# TDR1.net
KiCad netlist of a schematic drawn in EAGLE
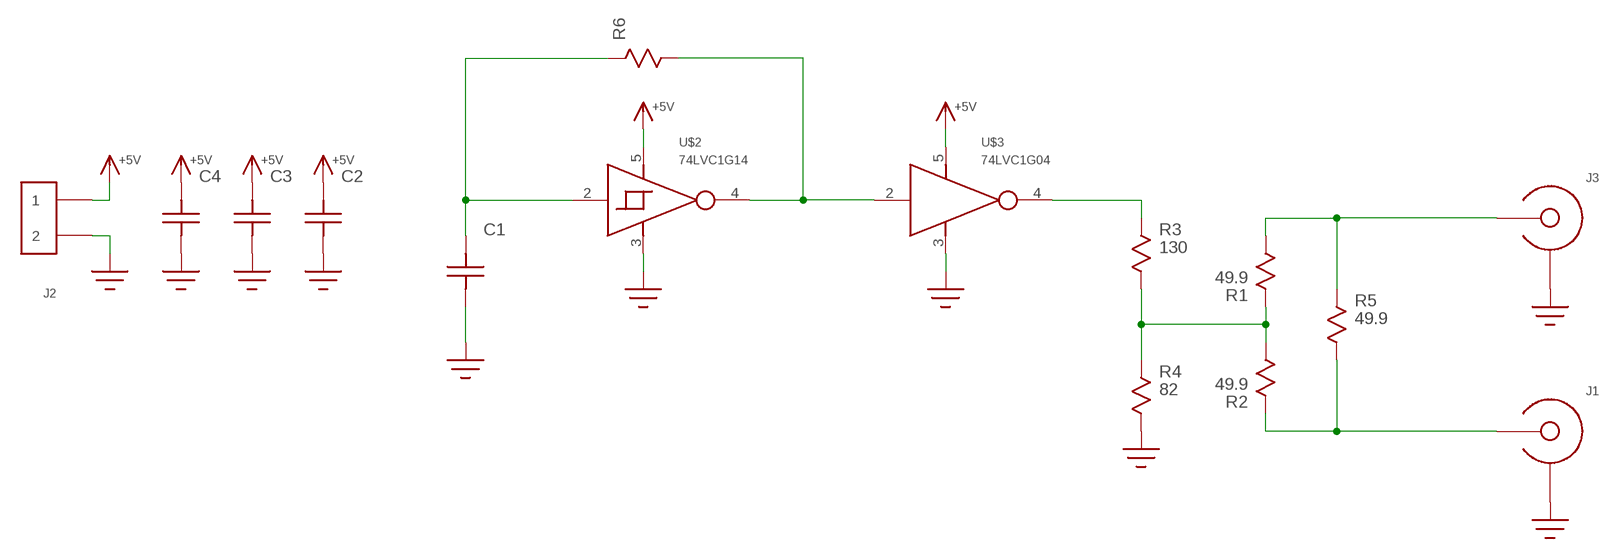
[diagram p0: schematic, sheet 1]

(export (version "E")
  (design (tool "Eeschema 10.0.6"))
  (components
    (comp (ref "C1")
      (value "C0603")
      (footprint "eagle-import:C0603")
      (libsource (lib "eagle-import") (part "C0603"))
    )
    (comp (ref "C2")
      (value "C0603")
      (footprint "eagle-import:C0603")
      (libsource (lib "eagle-import") (part "C0603"))
    )
    (comp (ref "C3")
      (value "C0603")
      (footprint "eagle-import:C0603")
      (libsource (lib "eagle-import") (part "C0603"))
    )
    (comp (ref "C4")
      (value "C1206")
      (footprint "eagle-import:1206")
      (libsource (lib "eagle-import") (part "C1206"))
    )
    (comp (ref "J1")
      (value "BNC_MALE_PCB")
      (footprint "eagle-import:BNC_MALE_PCB")
      (libsource (lib "eagle-import") (part "BNC_MALE_PCB"))
    )
    (comp (ref "J2")
      (value "HEADER_2PIN")
      (footprint "eagle-import:HEADER_2PIN")
      (libsource (lib "eagle-import") (part "HEADER_2PIN"))
    )
    (comp (ref "J3")
      (value "EDGE_LAUNCH_JACK")
      (footprint "eagle-import:EDGE_LAUNCH_RF_CON")
      (libsource (lib "eagle-import") (part "EDGE_LAUNCH_JACK"))
    )
    (comp (ref "R1")
      (value "49.9")
      (footprint "eagle-import:R0603")
      (libsource (lib "eagle-import") (part "R0603"))
    )
    (comp (ref "R2")
      (value "49.9")
      (footprint "eagle-import:R0603")
      (libsource (lib "eagle-import") (part "R0603"))
    )
    (comp (ref "R3")
      (value "130")
      (footprint "eagle-import:R0603")
      (libsource (lib "eagle-import") (part "R0603"))
    )
    (comp (ref "R4")
      (value "82")
      (footprint "eagle-import:R0603")
      (libsource (lib "eagle-import") (part "R0603"))
    )
    (comp (ref "R5")
      (value "49.9")
      (footprint "eagle-import:R0603")
      (libsource (lib "eagle-import") (part "R0603"))
    )
    (comp (ref "R6")
      (value "R0603")
      (footprint "eagle-import:R0603")
      (libsource (lib "eagle-import") (part "R0603"))
    )
    (comp (ref "U$2")
      (value "74LVC1G14")
      (footprint "eagle-import:SOT23-5")
      (libsource (lib "eagle-import") (part "74LVC1G14"))
    )
    (comp (ref "U$3")
      (value "74LVC1G04")
      (footprint "eagle-import:SOT23-5")
      (libsource (lib "eagle-import") (part "74LVC1G04"))
    )
  )
  (nets
    (net (code "1") (name "+5V") (class "Default")
      (node (ref "C2") (pin "P$2") (pinfunction "P$2_P$2") (pintype "bidirectional"))
      (node (ref "C3") (pin "P$2") (pinfunction "P$2_P$2") (pintype "bidirectional"))
      (node (ref "C4") (pin "P$2") (pinfunction "P$2_P$2") (pintype "bidirectional"))
      (node (ref "J2") (pin "1") (pinfunction "1_1") (pintype "bidirectional"))
      (node (ref "U$2") (pin "5") (pinfunction "VCC_5") (pintype "bidirectional"))
      (node (ref "U$3") (pin "5") (pinfunction "VCC_5") (pintype "bidirectional"))
    )
    (net (code "2") (name "GND") (class "Default")
      (node (ref "C1") (pin "P$1") (pinfunction "P$1_P$1") (pintype "bidirectional"))
      (node (ref "C2") (pin "P$1") (pinfunction "P$1_P$1") (pintype "bidirectional"))
      (node (ref "C3") (pin "P$1") (pinfunction "P$1_P$1") (pintype "bidirectional"))
      (node (ref "C4") (pin "P$1") (pinfunction "P$1_P$1") (pintype "bidirectional"))
      (node (ref "J1") (pin "SHIELD@1") (pinfunction "SHIELD_SHIELD@1") (pintype "bidirectional"))
      (node (ref "J1") (pin "SHIELD@2") (pinfunction "SHIELD_SHIELD@2") (pintype "bidirectional"))
      (node (ref "J1") (pin "SHIELD@3") (pinfunction "SHIELD_SHIELD@3") (pintype "bidirectional"))
      (node (ref "J1") (pin "SHIELD@4") (pinfunction "SHIELD_SHIELD@4") (pintype "bidirectional"))
      (node (ref "J2") (pin "2") (pinfunction "2_2") (pintype "bidirectional"))
      (node (ref "J3") (pin "GND@1") (pinfunction "SHIELD_GND@1") (pintype "bidirectional"))
      (node (ref "J3") (pin "GND@10") (pinfunction "SHIELD_GND@10") (pintype "bidirectional"))
      (node (ref "J3") (pin "GND@11") (pinfunction "SHIELD_GND@11") (pintype "bidirectional"))
      (node (ref "J3") (pin "GND@12") (pinfunction "SHIELD_GND@12") (pintype "bidirectional"))
      (node (ref "J3") (pin "GND@2") (pinfunction "SHIELD_GND@2") (pintype "bidirectional"))
      (node (ref "J3") (pin "GND@3") (pinfunction "SHIELD_GND@3") (pintype "bidirectional"))
      (node (ref "J3") (pin "GND@4") (pinfunction "SHIELD_GND@4") (pintype "bidirectional"))
      (node (ref "J3") (pin "GND@5") (pinfunction "SHIELD_GND@5") (pintype "bidirectional"))
      (node (ref "J3") (pin "GND@6") (pinfunction "SHIELD_GND@6") (pintype "bidirectional"))
      (node (ref "J3") (pin "GND@7") (pinfunction "SHIELD_GND@7") (pintype "bidirectional"))
      (node (ref "J3") (pin "GND@8") (pinfunction "SHIELD_GND@8") (pintype "bidirectional"))
      (node (ref "J3") (pin "GND@9") (pinfunction "SHIELD_GND@9") (pintype "bidirectional"))
      (node (ref "J3") (pin "SHIELD@1") (pinfunction "SHIELD_SHIELD@1") (pintype "bidirectional"))
      (node (ref "J3") (pin "SHIELD@2") (pinfunction "SHIELD_SHIELD@2") (pintype "bidirectional"))
      (node (ref "R4") (pin "P$2") (pinfunction "P$4_P$2") (pintype "bidirectional"))
      (node (ref "U$2") (pin "3") (pinfunction "GND_3") (pintype "bidirectional"))
      (node (ref "U$3") (pin "3") (pinfunction "GND_3") (pintype "bidirectional"))
    )
    (net (code "3") (name "Net-(R1-P$3)") (class "Default")
      (node (ref "R1") (pin "P$1") (pinfunction "P$3_P$1") (pintype "bidirectional"))
      (node (ref "R2") (pin "P$2") (pinfunction "P$4_P$2") (pintype "bidirectional"))
      (node (ref "R3") (pin "P$2") (pinfunction "P$4_P$2") (pintype "bidirectional"))
      (node (ref "R4") (pin "P$1") (pinfunction "P$3_P$1") (pintype "bidirectional"))
    )
    (net (code "4") (name "Net-(R1-P$4)") (class "Default")
      (node (ref "J3") (pin "CENTER") (pinfunction "CENTER_CENTER") (pintype "bidirectional"))
      (node (ref "R1") (pin "P$2") (pinfunction "P$4_P$2") (pintype "bidirectional"))
      (node (ref "R5") (pin "P$1") (pinfunction "P$3_P$1") (pintype "bidirectional"))
    )
    (net (code "5") (name "Net-(R2-P$3)") (class "Default")
      (node (ref "J1") (pin "CENTER") (pinfunction "CENTER_CENTER") (pintype "bidirectional"))
      (node (ref "R2") (pin "P$1") (pinfunction "P$3_P$1") (pintype "bidirectional"))
      (node (ref "R5") (pin "P$2") (pinfunction "P$4_P$2") (pintype "bidirectional"))
    )
    (net (code "6") (name "Net-(R3-P$3)") (class "Default")
      (node (ref "R3") (pin "P$1") (pinfunction "P$3_P$1") (pintype "bidirectional"))
      (node (ref "U$3") (pin "4") (pinfunction "OUT_4") (pintype "bidirectional"))
    )
    (net (code "7") (name "Net-(R6-P$3)") (class "Default")
      (node (ref "C1") (pin "P$2") (pinfunction "P$2_P$2") (pintype "bidirectional"))
      (node (ref "R6") (pin "P$1") (pinfunction "P$3_P$1") (pintype "bidirectional"))
      (node (ref "U$2") (pin "2") (pinfunction "IN_2") (pintype "bidirectional"))
    )
    (net (code "8") (name "Net-(R6-P$4)") (class "Default")
      (node (ref "R6") (pin "P$2") (pinfunction "P$4_P$2") (pintype "bidirectional"))
      (node (ref "U$2") (pin "4") (pinfunction "OUT_4") (pintype "bidirectional"))
      (node (ref "U$3") (pin "2") (pinfunction "IN_2") (pintype "bidirectional"))
    )
  )
)
